# I2C_MUX.net
KiCad netlist of a schematic drawn in EAGLE
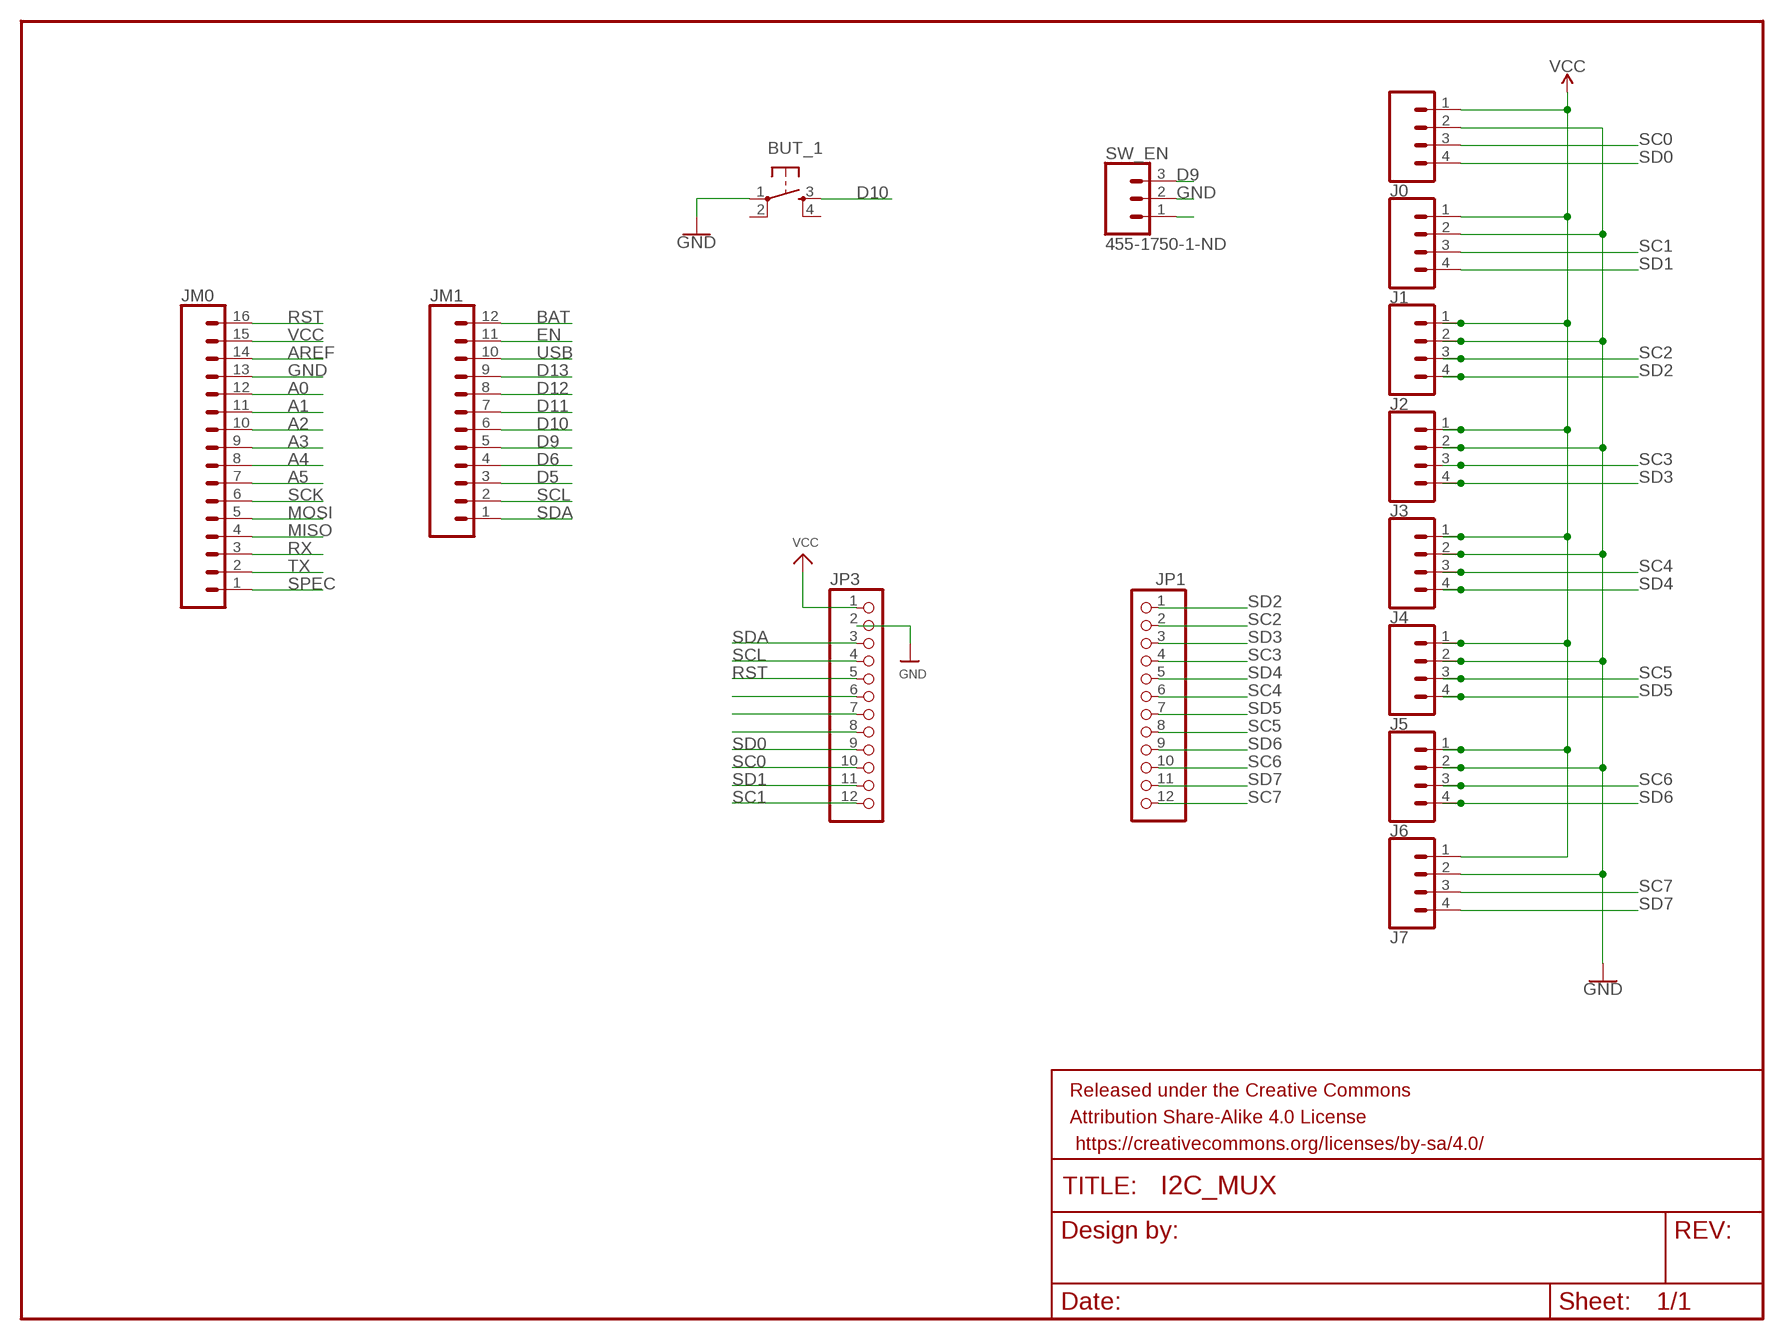
[diagram p0: schematic, sheet 1]

(export (version "E")
  (design (tool "Eeschema 10.0.6"))
  (components
    (comp (ref "BUT_1")
      (value "TAC_SWITCHPTH")
      (footprint "eagle-import:TACTILE-PTH")
      (libsource (lib "eagle-import") (part "TAC_SWITCHPTH"))
    )
    (comp (ref "FRAME1")
      (value "FRAME-LETTER")
      (footprint "eagle-import:CREATIVE_COMMONS")
      (libsource (lib "eagle-import") (part "FRAME-LETTER"))
    )
    (comp (ref "J0")
      (value "CONN_04POLAR")
      (footprint "eagle-import:MOLEX-1X4")
      (libsource (lib "eagle-import") (part "CONN_04POLAR"))
    )
    (comp (ref "J1")
      (value "CONN_04POLAR")
      (footprint "eagle-import:MOLEX-1X4")
      (libsource (lib "eagle-import") (part "CONN_04POLAR"))
    )
    (comp (ref "J2")
      (value "CONN_04POLAR")
      (footprint "eagle-import:MOLEX-1X4")
      (libsource (lib "eagle-import") (part "CONN_04POLAR"))
    )
    (comp (ref "J3")
      (value "CONN_04POLAR")
      (footprint "eagle-import:MOLEX-1X4")
      (libsource (lib "eagle-import") (part "CONN_04POLAR"))
    )
    (comp (ref "J4")
      (value "CONN_04POLAR")
      (footprint "eagle-import:MOLEX-1X4")
      (libsource (lib "eagle-import") (part "CONN_04POLAR"))
    )
    (comp (ref "J5")
      (value "CONN_04POLAR")
      (footprint "eagle-import:MOLEX-1X4")
      (libsource (lib "eagle-import") (part "CONN_04POLAR"))
    )
    (comp (ref "J6")
      (value "CONN_04POLAR")
      (footprint "eagle-import:MOLEX-1X4")
      (libsource (lib "eagle-import") (part "CONN_04POLAR"))
    )
    (comp (ref "J7")
      (value "CONN_04POLAR")
      (footprint "eagle-import:MOLEX-1X4")
      (libsource (lib "eagle-import") (part "CONN_04POLAR"))
    )
    (comp (ref "JM0")
      (value "CONN_16")
      (footprint "eagle-import:1X16")
      (libsource (lib "eagle-import") (part "CONN_16"))
    )
    (comp (ref "JM1")
      (value "CONN_12")
      (footprint "eagle-import:1X12")
      (libsource (lib "eagle-import") (part "CONN_12"))
    )
    (comp (ref "JP1")
      (value "HEADER-1X12")
      (footprint "eagle-import:1X12_ROUND")
      (libsource (lib "eagle-import") (part "HEADER-1X12"))
    )
    (comp (ref "JP3")
      (value "HEADER-1X12")
      (footprint "eagle-import:1X12_ROUND")
      (libsource (lib "eagle-import") (part "HEADER-1X12"))
    )
    (comp (ref "SW_EN")
      (value "455-1750-1-ND")
      (footprint "eagle-import:1X03")
      (libsource (lib "eagle-import") (part "CONN_03"))
    )
  )
  (nets
    (net (code "1") (name "/A0") (class "Default")
      (node (ref "JM0") (pin "12") (pinfunction "12_12") (pintype "passive"))
    )
    (net (code "2") (name "/A1") (class "Default")
      (node (ref "JM0") (pin "11") (pinfunction "11_11") (pintype "passive"))
    )
    (net (code "3") (name "/A2") (class "Default")
      (node (ref "JM0") (pin "10") (pinfunction "10_10") (pintype "passive"))
    )
    (net (code "4") (name "/A3") (class "Default")
      (node (ref "JM0") (pin "9") (pinfunction "9_9") (pintype "passive"))
    )
    (net (code "5") (name "/A4") (class "Default")
      (node (ref "JM0") (pin "8") (pinfunction "8_8") (pintype "passive"))
    )
    (net (code "6") (name "/A5") (class "Default")
      (node (ref "JM0") (pin "7") (pinfunction "7_7") (pintype "passive"))
    )
    (net (code "7") (name "/AREF") (class "Default")
      (node (ref "JM0") (pin "14") (pinfunction "14_14") (pintype "passive"))
    )
    (net (code "8") (name "/BAT") (class "Default")
      (node (ref "JM1") (pin "12") (pinfunction "12_12") (pintype "passive"))
    )
    (net (code "9") (name "/D5") (class "Default")
      (node (ref "JM1") (pin "3") (pinfunction "3_3") (pintype "passive"))
    )
    (net (code "10") (name "/D6") (class "Default")
      (node (ref "JM1") (pin "4") (pinfunction "4_4") (pintype "passive"))
    )
    (net (code "11") (name "/D9") (class "Default")
      (node (ref "JM1") (pin "5") (pinfunction "5_5") (pintype "passive"))
      (node (ref "SW_EN") (pin "3") (pinfunction "3_3") (pintype "passive"))
    )
    (net (code "12") (name "/D10") (class "Default")
      (node (ref "BUT_1") (pin "3") (pinfunction "3_3") (pintype "passive"))
      (node (ref "JM1") (pin "6") (pinfunction "6_6") (pintype "passive"))
    )
    (net (code "13") (name "/D11") (class "Default")
      (node (ref "JM1") (pin "7") (pinfunction "7_7") (pintype "passive"))
    )
    (net (code "14") (name "/D12") (class "Default")
      (node (ref "JM1") (pin "8") (pinfunction "8_8") (pintype "passive"))
    )
    (net (code "15") (name "/D13") (class "Default")
      (node (ref "JM1") (pin "9") (pinfunction "9_9") (pintype "passive"))
    )
    (net (code "16") (name "/EN") (class "Default")
      (node (ref "JM1") (pin "11") (pinfunction "11_11") (pintype "passive"))
    )
    (net (code "17") (name "/MISO") (class "Default")
      (node (ref "JM0") (pin "4") (pinfunction "4_4") (pintype "passive"))
    )
    (net (code "18") (name "/MOSI") (class "Default")
      (node (ref "JM0") (pin "5") (pinfunction "5_5") (pintype "passive"))
    )
    (net (code "19") (name "/RST") (class "Default")
      (node (ref "JM0") (pin "16") (pinfunction "16_16") (pintype "passive"))
      (node (ref "JP3") (pin "5") (pinfunction "5_5") (pintype "passive"))
    )
    (net (code "20") (name "/RX") (class "Default")
      (node (ref "JM0") (pin "3") (pinfunction "3_3") (pintype "passive"))
    )
    (net (code "21") (name "/SC0") (class "Default")
      (node (ref "J0") (pin "3") (pinfunction "3_3") (pintype "passive"))
      (node (ref "JP3") (pin "10") (pinfunction "10_10") (pintype "passive"))
    )
    (net (code "22") (name "/SC1") (class "Default")
      (node (ref "J1") (pin "3") (pinfunction "3_3") (pintype "passive"))
      (node (ref "JP3") (pin "12") (pinfunction "12_12") (pintype "passive"))
    )
    (net (code "23") (name "/SC2") (class "Default")
      (node (ref "J2") (pin "3") (pinfunction "3_3") (pintype "passive"))
      (node (ref "JP1") (pin "2") (pinfunction "2_2") (pintype "passive"))
    )
    (net (code "24") (name "/SC3") (class "Default")
      (node (ref "J3") (pin "3") (pinfunction "3_3") (pintype "passive"))
      (node (ref "JP1") (pin "4") (pinfunction "4_4") (pintype "passive"))
    )
    (net (code "25") (name "/SC4") (class "Default")
      (node (ref "J4") (pin "3") (pinfunction "3_3") (pintype "passive"))
      (node (ref "JP1") (pin "6") (pinfunction "6_6") (pintype "passive"))
    )
    (net (code "26") (name "/SC5") (class "Default")
      (node (ref "J5") (pin "3") (pinfunction "3_3") (pintype "passive"))
      (node (ref "JP1") (pin "8") (pinfunction "8_8") (pintype "passive"))
    )
    (net (code "27") (name "/SC6") (class "Default")
      (node (ref "J6") (pin "3") (pinfunction "3_3") (pintype "passive"))
      (node (ref "JP1") (pin "10") (pinfunction "10_10") (pintype "passive"))
    )
    (net (code "28") (name "/SC7") (class "Default")
      (node (ref "J7") (pin "3") (pinfunction "3_3") (pintype "passive"))
      (node (ref "JP1") (pin "12") (pinfunction "12_12") (pintype "passive"))
    )
    (net (code "29") (name "/SCK") (class "Default")
      (node (ref "JM0") (pin "6") (pinfunction "6_6") (pintype "passive"))
    )
    (net (code "30") (name "/SCL") (class "Default")
      (node (ref "JM1") (pin "2") (pinfunction "2_2") (pintype "passive"))
      (node (ref "JP3") (pin "4") (pinfunction "4_4") (pintype "passive"))
    )
    (net (code "31") (name "/SD0") (class "Default")
      (node (ref "J0") (pin "4") (pinfunction "4_4") (pintype "passive"))
      (node (ref "JP3") (pin "9") (pinfunction "9_9") (pintype "passive"))
    )
    (net (code "32") (name "/SD1") (class "Default")
      (node (ref "J1") (pin "4") (pinfunction "4_4") (pintype "passive"))
      (node (ref "JP3") (pin "11") (pinfunction "11_11") (pintype "passive"))
    )
    (net (code "33") (name "/SD2") (class "Default")
      (node (ref "J2") (pin "4") (pinfunction "4_4") (pintype "passive"))
      (node (ref "JP1") (pin "1") (pinfunction "1_1") (pintype "passive"))
    )
    (net (code "34") (name "/SD3") (class "Default")
      (node (ref "J3") (pin "4") (pinfunction "4_4") (pintype "passive"))
      (node (ref "JP1") (pin "3") (pinfunction "3_3") (pintype "passive"))
    )
    (net (code "35") (name "/SD4") (class "Default")
      (node (ref "J4") (pin "4") (pinfunction "4_4") (pintype "passive"))
      (node (ref "JP1") (pin "5") (pinfunction "5_5") (pintype "passive"))
    )
    (net (code "36") (name "/SD5") (class "Default")
      (node (ref "J5") (pin "4") (pinfunction "4_4") (pintype "passive"))
      (node (ref "JP1") (pin "7") (pinfunction "7_7") (pintype "passive"))
    )
    (net (code "37") (name "/SD6") (class "Default")
      (node (ref "J6") (pin "4") (pinfunction "4_4") (pintype "passive"))
      (node (ref "JP1") (pin "9") (pinfunction "9_9") (pintype "passive"))
    )
    (net (code "38") (name "/SD7") (class "Default")
      (node (ref "J7") (pin "4") (pinfunction "4_4") (pintype "passive"))
      (node (ref "JP1") (pin "11") (pinfunction "11_11") (pintype "passive"))
    )
    (net (code "39") (name "/SDA") (class "Default")
      (node (ref "JM1") (pin "1") (pinfunction "1_1") (pintype "passive"))
      (node (ref "JP3") (pin "3") (pinfunction "3_3") (pintype "passive"))
    )
    (net (code "40") (name "/SPEC") (class "Default")
      (node (ref "JM0") (pin "1") (pinfunction "1_1") (pintype "passive"))
    )
    (net (code "41") (name "/TX") (class "Default")
      (node (ref "JM0") (pin "2") (pinfunction "2_2") (pintype "passive"))
    )
    (net (code "42") (name "/USB") (class "Default")
      (node (ref "JM1") (pin "10") (pinfunction "10_10") (pintype "passive"))
    )
    (net (code "43") (name "GND") (class "Default")
      (node (ref "BUT_1") (pin "1") (pinfunction "1_1") (pintype "passive"))
      (node (ref "J0") (pin "2") (pinfunction "2_2") (pintype "passive"))
      (node (ref "J1") (pin "2") (pinfunction "2_2") (pintype "passive"))
      (node (ref "J2") (pin "2") (pinfunction "2_2") (pintype "passive"))
      (node (ref "J3") (pin "2") (pinfunction "2_2") (pintype "passive"))
      (node (ref "J4") (pin "2") (pinfunction "2_2") (pintype "passive"))
      (node (ref "J5") (pin "2") (pinfunction "2_2") (pintype "passive"))
      (node (ref "J6") (pin "2") (pinfunction "2_2") (pintype "passive"))
      (node (ref "J7") (pin "2") (pinfunction "2_2") (pintype "passive"))
      (node (ref "JM0") (pin "13") (pinfunction "13_13") (pintype "passive"))
      (node (ref "JP3") (pin "2") (pinfunction "2_2") (pintype "passive"))
      (node (ref "SW_EN") (pin "2") (pinfunction "2_2") (pintype "passive"))
    )
    (net (code "44") (name "VCC") (class "Default")
      (node (ref "J0") (pin "1") (pinfunction "1_1") (pintype "passive"))
      (node (ref "J1") (pin "1") (pinfunction "1_1") (pintype "passive"))
      (node (ref "J2") (pin "1") (pinfunction "1_1") (pintype "passive"))
      (node (ref "J3") (pin "1") (pinfunction "1_1") (pintype "passive"))
      (node (ref "J4") (pin "1") (pinfunction "1_1") (pintype "passive"))
      (node (ref "J5") (pin "1") (pinfunction "1_1") (pintype "passive"))
      (node (ref "J6") (pin "1") (pinfunction "1_1") (pintype "passive"))
      (node (ref "J7") (pin "1") (pinfunction "1_1") (pintype "passive"))
      (node (ref "JM0") (pin "15") (pinfunction "15_15") (pintype "passive"))
      (node (ref "JP3") (pin "1") (pinfunction "1_1") (pintype "passive"))
    )
    (net (code "45") (name "unconnected-(BUT_1-Pad2)") (class "Default")
      (node (ref "BUT_1") (pin "2") (pinfunction "2_2") (pintype "passive"))
    )
    (net (code "46") (name "unconnected-(BUT_1-Pad4)") (class "Default")
      (node (ref "BUT_1") (pin "4") (pinfunction "4_4") (pintype "passive"))
    )
    (net (code "47") (name "unconnected-(JP3-Pad6)") (class "Default")
      (node (ref "JP3") (pin "6") (pinfunction "6_6") (pintype "passive"))
    )
    (net (code "48") (name "unconnected-(JP3-Pad7)") (class "Default")
      (node (ref "JP3") (pin "7") (pinfunction "7_7") (pintype "passive"))
    )
    (net (code "49") (name "unconnected-(JP3-Pad8)") (class "Default")
      (node (ref "JP3") (pin "8") (pinfunction "8_8") (pintype "passive"))
    )
    (net (code "50") (name "unconnected-(SW_EN-Pad1)") (class "Default")
      (node (ref "SW_EN") (pin "1") (pinfunction "1_1") (pintype "passive"))
    )
  )
)
